# Main.net
KiCad netlist of a schematic drawn in Altium Designer
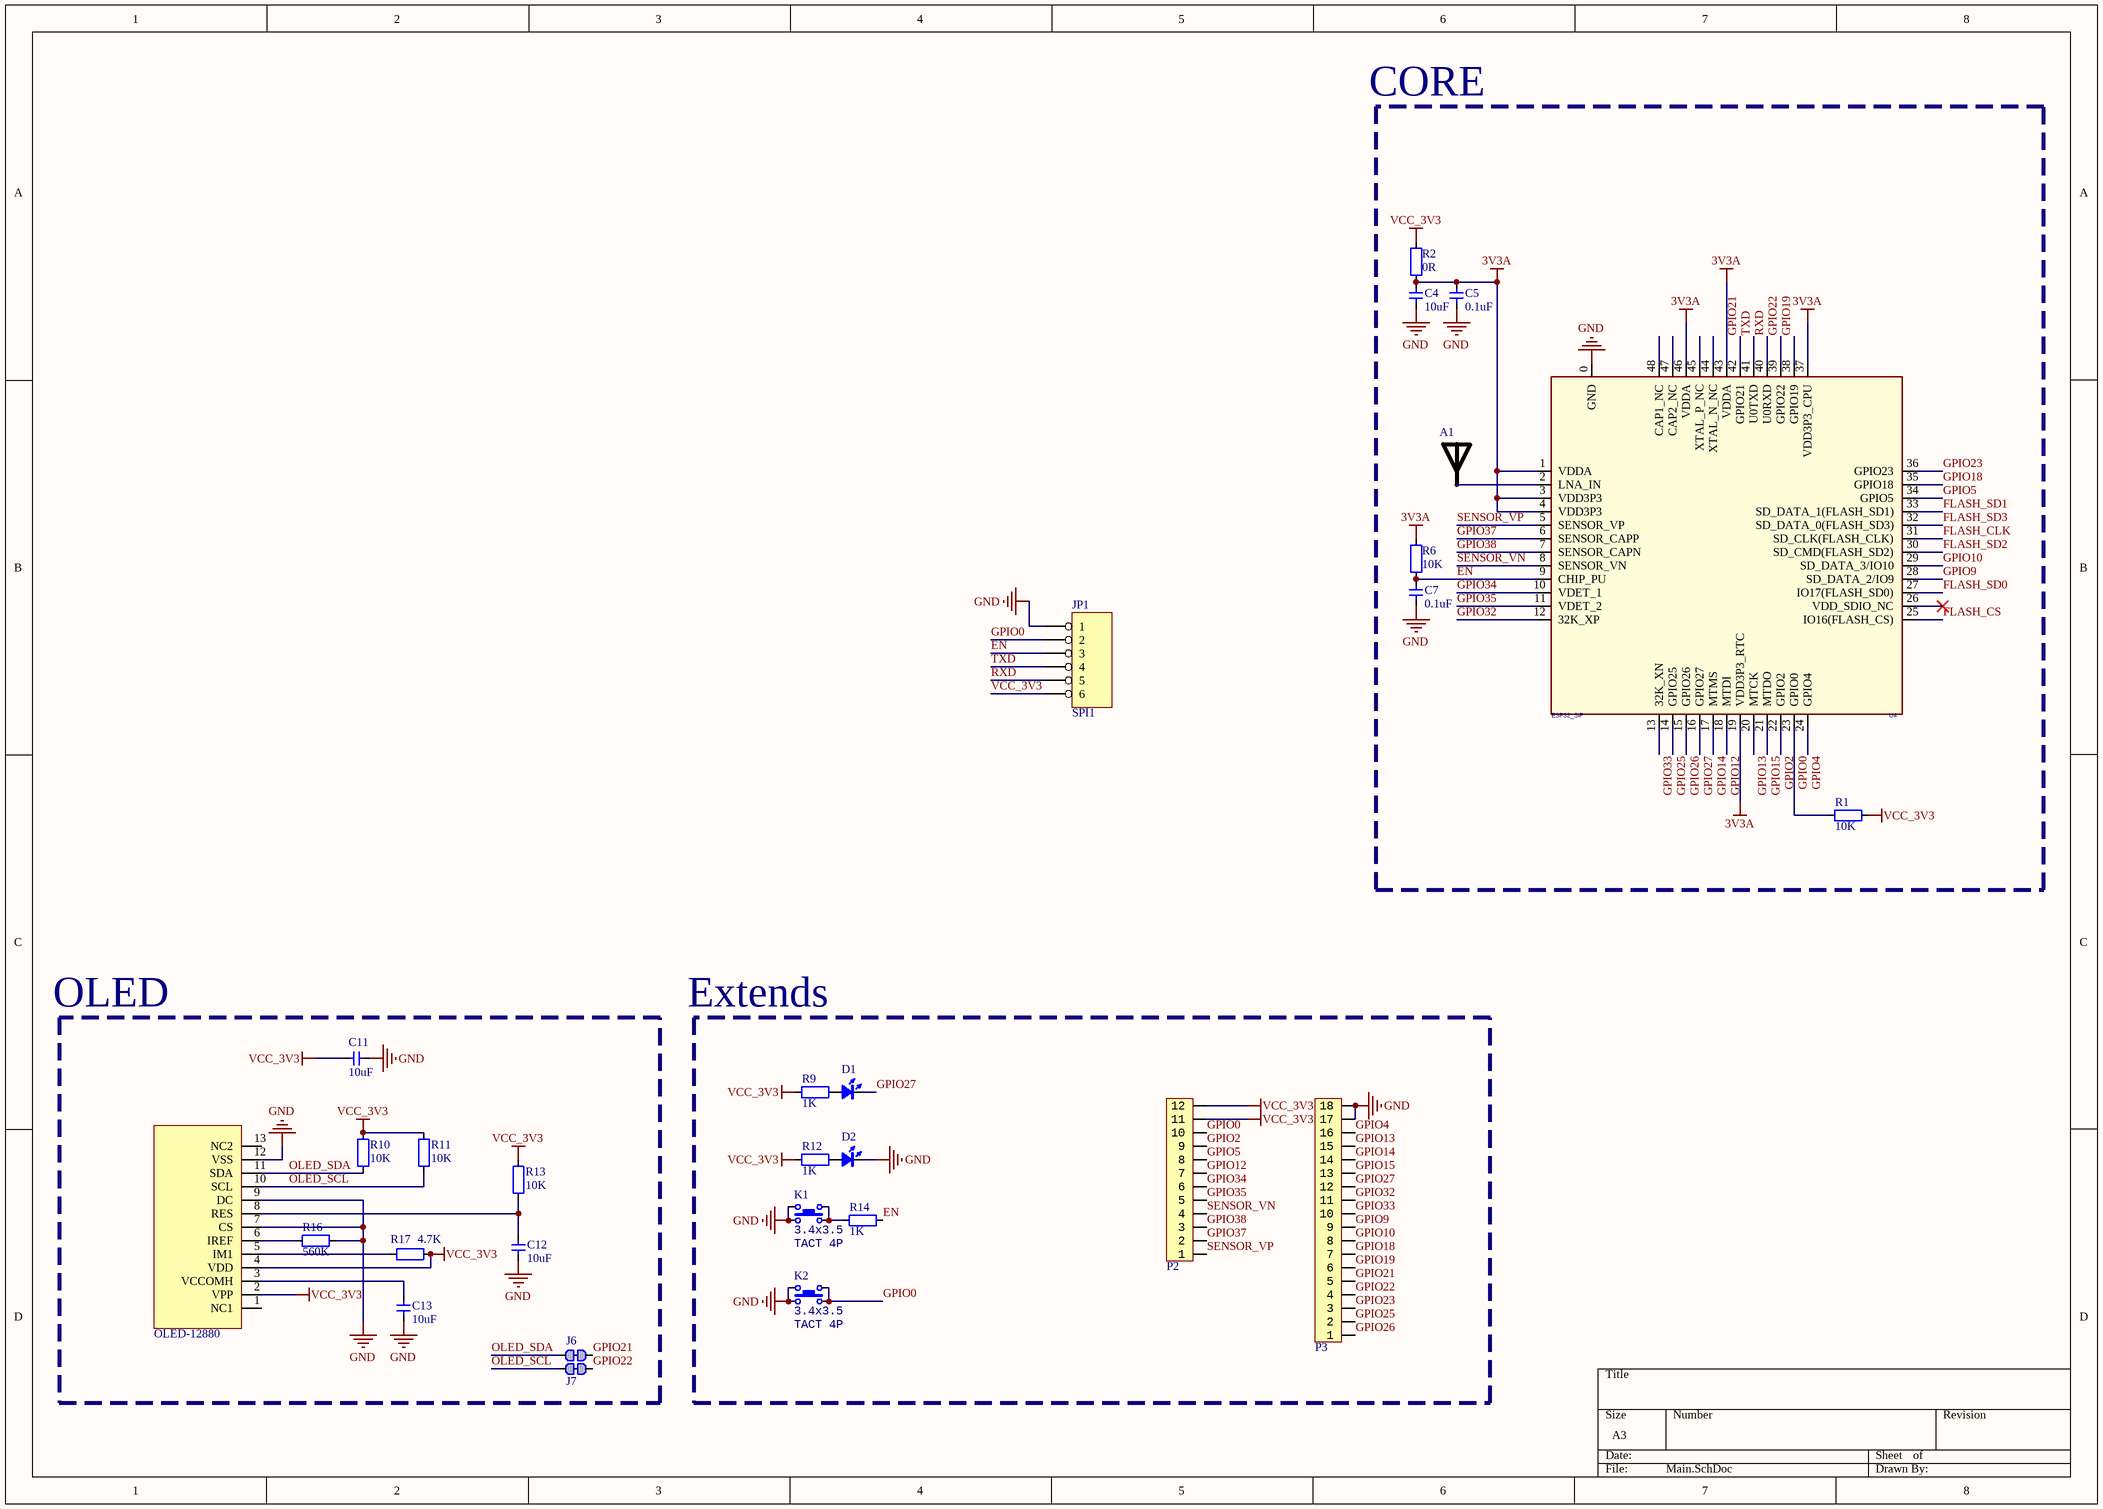
[diagram p0: Main.SchDoc]

(export (version "E")
  (design (tool "Eeschema 10.0.6"))
  (components
    (comp (ref "1")
      (value "OLED-12880")
      (footprint "OLED-12880")
      (libsource (lib "mLib") (part "OLED-12880"))
    )
    (comp (ref "A1")
      (value "RAINSUN")
      (footprint "ANT-Rainsun-AN5120")
      (libsource (lib "MyPcbLib") (part "ANT-Rainsun-AP5120"))
    )
    (comp (ref "C4")
      (value "10uF")
      (footprint "CAP_0402")
      (description "Capacitor")
      (libsource (lib "MyPcbLib") (part "电容-0402"))
    )
    (comp (ref "C5")
      (value "0.1uF")
      (footprint "CAP_0402")
      (description "Capacitor")
      (libsource (lib "MyPcbLib") (part "电容-0402"))
    )
    (comp (ref "C7")
      (value "0.1uF")
      (footprint "CAP_0402")
      (description "Capacitor")
      (libsource (lib "MyPcbLib") (part "电容-0402"))
    )
    (comp (ref "C11")
      (value "10uF")
      (footprint "CAP_0402")
      (description "Capacitor")
      (libsource (lib "MyPcbLib") (part "电容-0402"))
    )
    (comp (ref "C12")
      (value "10uF")
      (footprint "CAP_0402")
      (description "Capacitor")
      (libsource (lib "MyPcbLib") (part "电容-0402"))
    )
    (comp (ref "C13")
      (value "10uF")
      (footprint "CAP_0402")
      (description "Capacitor")
      (libsource (lib "MyPcbLib") (part "电容-0402"))
    )
    (comp (ref "D1")
      (value "color?")
      (footprint "LED_0402_RED")
      (description "LED")
      (libsource (lib "KitSprout") (part "LED_0402"))
    )
    (comp (ref "D2")
      (value "color?")
      (footprint "LED_0402_RED")
      (description "LED")
      (libsource (lib "KitSprout") (part "LED_0402"))
    )
    (comp (ref "J6")
      (value "跳线")
      (footprint "0402-0R")
      (description "Resistor")
      (fields (field (name "PUBLISHER") "Altium Limited"))
      (libsource (lib "MyPcbLib") (part "跳线"))
    )
    (comp (ref "J7")
      (value "跳线")
      (footprint "0402-0R")
      (description "Resistor")
      (fields (field (name "PUBLISHER") "Altium Limited"))
      (libsource (lib "MyPcbLib") (part "跳线"))
    )
    (comp (ref "JP1")
      (value "SPI1")
      (footprint "CONN-SMD_6P-P1.25_DEALON_1.25-6PWB")
      (libsource (lib "刘涛20200314") (part "HEADER 6"))
    )
    (comp (ref "K1")
      (value "3.4x3.5")
      (footprint "ButtonTACT_3.5*3.55_90")
      (description "Button")
      (fields (field (name "TYPE") "TACT 4P") (field (name "Comment") "TACT 4P"))
      (libsource (lib "KitSprout") (part "ButtonTACT"))
    )
    (comp (ref "K2")
      (value "3.4x3.5")
      (footprint "ButtonTACT_3.5*3.55_90")
      (description "Button")
      (fields (field (name "TYPE") "TACT 4P") (field (name "Comment") "TACT 4P"))
      (libsource (lib "KitSprout") (part "ButtonTACT"))
    )
    (comp (ref "P2")
      (value "HDR1x12_2.54")
      (footprint "HDR1X12_2.54_180")
      (description "Header")
      (libsource (lib "KitSprout") (part "HDR1x12_2.54"))
    )
    (comp (ref "P3")
      (value "HDR1x18_2.54")
      (footprint "HDR1X18_2.54_180")
      (description "Header")
      (libsource (lib "KitSprout") (part "HDR1x18_2.54"))
    )
    (comp (ref "R1")
      (value "10K")
      (footprint "RES_0402")
      (description "Resistor")
      (libsource (lib "") (part "电阻-0402_1"))
    )
    (comp (ref "R2")
      (value "0R")
      (footprint "RES_0402")
      (description "Resistor")
      (libsource (lib "") (part "电阻-0402_2"))
    )
    (comp (ref "R6")
      (value "10K")
      (footprint "RES_0402")
      (description "Resistor")
      (libsource (lib "") (part "电阻-0402_2"))
    )
    (comp (ref "R9")
      (value "1K")
      (footprint "RES_0402")
      (description "Resistor")
      (libsource (lib "") (part "电阻-0402_1"))
    )
    (comp (ref "R10")
      (value "10K")
      (footprint "RES_0402")
      (description "Resistor")
      (libsource (lib "MyPcbLib") (part "电阻-0402"))
    )
    (comp (ref "R11")
      (value "10K")
      (footprint "RES_0402")
      (description "Resistor")
      (libsource (lib "MyPcbLib") (part "电阻-0402"))
    )
    (comp (ref "R12")
      (value "1K")
      (footprint "RES_0402")
      (description "Resistor")
      (libsource (lib "") (part "电阻-0402_1"))
    )
    (comp (ref "R13")
      (value "10K")
      (footprint "RES_0402")
      (description "Resistor")
      (libsource (lib "MyPcbLib") (part "电阻-0402"))
    )
    (comp (ref "R14")
      (value "1K")
      (footprint "RES_0402")
      (description "Resistor")
      (libsource (lib "") (part "电阻-0402_1"))
    )
    (comp (ref "R16")
      (value "560K")
      (footprint "RES_0402")
      (description "Resistor")
      (libsource (lib "") (part "电阻-0402_1"))
    )
    (comp (ref "R17")
      (value "4.7K")
      (footprint "RES_0402")
      (description "Resistor")
      (libsource (lib "") (part "电阻-0402_1"))
    )
    (comp (ref "U4")
      (value "ESP32_SIP")
      (footprint "QFN-48_7X7")
      (libsource (lib "MyPcbLib") (part "ESP32-PICO"))
    )
  )
  (nets
    (net (code "1") (name "/EN") (class "Default")
      (node (ref "C7") (pin "1") (pinfunction "1_1") (pintype "passive"))
      (node (ref "JP1") (pin "3") (pinfunction "3_3") (pintype "passive"))
      (node (ref "R14") (pin "2") (pinfunction "2_2") (pintype "passive"))
      (node (ref "R6") (pin "2") (pinfunction "2_2") (pintype "passive"))
      (node (ref "U4") (pin "9") (pinfunction "CHIP_PU_9") (pintype "passive"))
    )
    (net (code "2") (name "/FLASH_CLK") (class "Default")
      (node (ref "U4") (pin "31") (pinfunction "SD_CLK(FLASH_CLK)_31") (pintype "passive"))
    )
    (net (code "3") (name "/FLASH_CS") (class "Default")
      (node (ref "U4") (pin "25") (pinfunction "IO16(FLASH_CS)_25") (pintype "passive"))
    )
    (net (code "4") (name "/FLASH_SD0") (class "Default")
      (node (ref "U4") (pin "27") (pinfunction "IO17(FLASH_SD0)_27") (pintype "passive"))
    )
    (net (code "5") (name "/FLASH_SD1") (class "Default")
      (node (ref "U4") (pin "33") (pinfunction "SD_DATA_1(FLASH_SD1)_33") (pintype "passive"))
    )
    (net (code "6") (name "/FLASH_SD2") (class "Default")
      (node (ref "U4") (pin "30") (pinfunction "SD_CMD(FLASH_SD2)_30") (pintype "passive"))
    )
    (net (code "7") (name "/FLASH_SD3") (class "Default")
      (node (ref "U4") (pin "32") (pinfunction "SD_DATA_0(FLASH_SD3)_32") (pintype "passive"))
    )
    (net (code "8") (name "/GPIO0") (class "Default")
      (node (ref "JP1") (pin "2") (pinfunction "2_2") (pintype "passive"))
      (node (ref "K2") (pin "2") (pinfunction "2_2") (pintype "passive"))
      (node (ref "K2") (pin "4") (pinfunction "4_4") (pintype "passive"))
      (node (ref "P2") (pin "10") (pinfunction "10_10") (pintype "passive"))
      (node (ref "R1") (pin "1") (pinfunction "1_1") (pintype "passive"))
      (node (ref "U4") (pin "23") (pinfunction "GPIO0_23") (pintype "passive"))
    )
    (net (code "9") (name "/GPIO2") (class "Default")
      (node (ref "P2") (pin "9") (pinfunction "9_9") (pintype "passive"))
      (node (ref "U4") (pin "22") (pinfunction "GPIO2_22") (pintype "passive"))
    )
    (net (code "10") (name "/GPIO4") (class "Default")
      (node (ref "P3") (pin "16") (pinfunction "16_16") (pintype "passive"))
      (node (ref "U4") (pin "24") (pinfunction "GPIO4_24") (pintype "passive"))
    )
    (net (code "11") (name "/GPIO5") (class "Default")
      (node (ref "P2") (pin "8") (pinfunction "8_8") (pintype "passive"))
      (node (ref "U4") (pin "34") (pinfunction "GPIO5_34") (pintype "passive"))
    )
    (net (code "12") (name "/GPIO9") (class "Default")
      (node (ref "P3") (pin "9") (pinfunction "9_9") (pintype "passive"))
      (node (ref "U4") (pin "28") (pinfunction "SD_DATA_2/IO9_28") (pintype "passive"))
    )
    (net (code "13") (name "/GPIO10") (class "Default")
      (node (ref "P3") (pin "8") (pinfunction "8_8") (pintype "passive"))
      (node (ref "U4") (pin "29") (pinfunction "SD_DATA_3/IO10_29") (pintype "passive"))
    )
    (net (code "14") (name "/GPIO12") (class "Default")
      (node (ref "P2") (pin "7") (pinfunction "7_7") (pintype "passive"))
      (node (ref "U4") (pin "18") (pinfunction "MTDI_18") (pintype "passive"))
    )
    (net (code "15") (name "/GPIO13") (class "Default")
      (node (ref "P3") (pin "15") (pinfunction "15_15") (pintype "passive"))
      (node (ref "U4") (pin "20") (pinfunction "MTCK_20") (pintype "passive"))
    )
    (net (code "16") (name "/GPIO14") (class "Default")
      (node (ref "P3") (pin "14") (pinfunction "14_14") (pintype "passive"))
      (node (ref "U4") (pin "17") (pinfunction "MTMS_17") (pintype "passive"))
    )
    (net (code "17") (name "/GPIO15") (class "Default")
      (node (ref "P3") (pin "13") (pinfunction "13_13") (pintype "passive"))
      (node (ref "U4") (pin "21") (pinfunction "MTDO_21") (pintype "passive"))
    )
    (net (code "18") (name "/GPIO18") (class "Default")
      (node (ref "P3") (pin "7") (pinfunction "7_7") (pintype "passive"))
      (node (ref "U4") (pin "35") (pinfunction "GPIO18_35") (pintype "passive"))
    )
    (net (code "19") (name "/GPIO19") (class "Default")
      (node (ref "P3") (pin "6") (pinfunction "6_6") (pintype "passive"))
      (node (ref "U4") (pin "38") (pinfunction "GPIO19_38") (pintype "passive"))
    )
    (net (code "20") (name "/GPIO21") (class "Default")
      (node (ref "J6") (pin "2") (pinfunction "2_2") (pintype "passive"))
      (node (ref "P3") (pin "5") (pinfunction "5_5") (pintype "passive"))
      (node (ref "U4") (pin "42") (pinfunction "GPIO21_42") (pintype "passive"))
    )
    (net (code "21") (name "/GPIO22") (class "Default")
      (node (ref "J7") (pin "2") (pinfunction "2_2") (pintype "passive"))
      (node (ref "P3") (pin "4") (pinfunction "4_4") (pintype "passive"))
      (node (ref "U4") (pin "39") (pinfunction "GPIO22_39") (pintype "passive"))
    )
    (net (code "22") (name "/GPIO23") (class "Default")
      (node (ref "P3") (pin "3") (pinfunction "3_3") (pintype "passive"))
      (node (ref "U4") (pin "36") (pinfunction "GPIO23_36") (pintype "passive"))
    )
    (net (code "23") (name "/GPIO25") (class "Default")
      (node (ref "P3") (pin "2") (pinfunction "2_2") (pintype "passive"))
      (node (ref "U4") (pin "14") (pinfunction "GPIO25_14") (pintype "passive"))
    )
    (net (code "24") (name "/GPIO26") (class "Default")
      (node (ref "P3") (pin "1") (pinfunction "1_1") (pintype "passive"))
      (node (ref "U4") (pin "15") (pinfunction "GPIO26_15") (pintype "passive"))
    )
    (net (code "25") (name "/GPIO27") (class "Default")
      (node (ref "D1") (pin "2") (pinfunction "K_2") (pintype "passive"))
      (node (ref "P3") (pin "12") (pinfunction "12_12") (pintype "passive"))
      (node (ref "U4") (pin "16") (pinfunction "GPIO27_16") (pintype "passive"))
    )
    (net (code "26") (name "/GPIO32") (class "Default")
      (node (ref "P3") (pin "11") (pinfunction "11_11") (pintype "passive"))
      (node (ref "U4") (pin "12") (pinfunction "32K_XP_12") (pintype "passive"))
    )
    (net (code "27") (name "/GPIO33") (class "Default")
      (node (ref "P3") (pin "10") (pinfunction "10_10") (pintype "passive"))
      (node (ref "U4") (pin "13") (pinfunction "32K_XN_13") (pintype "passive"))
    )
    (net (code "28") (name "/GPIO34") (class "Default")
      (node (ref "P2") (pin "6") (pinfunction "6_6") (pintype "passive"))
      (node (ref "U4") (pin "10") (pinfunction "VDET_1_10") (pintype "passive"))
    )
    (net (code "29") (name "/GPIO35") (class "Default")
      (node (ref "P2") (pin "5") (pinfunction "5_5") (pintype "passive"))
      (node (ref "U4") (pin "11") (pinfunction "VDET_2_11") (pintype "passive"))
    )
    (net (code "30") (name "/GPIO37") (class "Default")
      (node (ref "P2") (pin "2") (pinfunction "2_2") (pintype "passive"))
      (node (ref "U4") (pin "6") (pinfunction "SENSOR_CAPP_6") (pintype "passive"))
    )
    (net (code "31") (name "/GPIO38") (class "Default")
      (node (ref "P2") (pin "3") (pinfunction "3_3") (pintype "passive"))
      (node (ref "U4") (pin "7") (pinfunction "SENSOR_CAPN_7") (pintype "passive"))
    )
    (net (code "32") (name "/OLED_SCL") (class "Default")
      (node (ref "1") (pin "10") (pinfunction "SCL_10") (pintype "passive"))
      (node (ref "J7") (pin "1") (pinfunction "1_1") (pintype "passive"))
      (node (ref "R11") (pin "1") (pinfunction "1_1") (pintype "passive"))
    )
    (net (code "33") (name "/OLED_SDA") (class "Default")
      (node (ref "1") (pin "11") (pinfunction "SDA_11") (pintype "passive"))
      (node (ref "J6") (pin "1") (pinfunction "1_1") (pintype "passive"))
      (node (ref "R10") (pin "1") (pinfunction "1_1") (pintype "passive"))
    )
    (net (code "34") (name "/RXD") (class "Default")
      (node (ref "JP1") (pin "5") (pinfunction "5_5") (pintype "passive"))
      (node (ref "U4") (pin "40") (pinfunction "U0RXD_40") (pintype "power_in"))
    )
    (net (code "35") (name "/SENSOR_VN") (class "Default")
      (node (ref "P2") (pin "4") (pinfunction "4_4") (pintype "passive"))
      (node (ref "U4") (pin "8") (pinfunction "SENSOR_VN_8") (pintype "passive"))
    )
    (net (code "36") (name "/SENSOR_VP") (class "Default")
      (node (ref "P2") (pin "1") (pinfunction "1_1") (pintype "passive"))
      (node (ref "U4") (pin "5") (pinfunction "SENSOR_VP_5") (pintype "passive"))
    )
    (net (code "37") (name "/TXD") (class "Default")
      (node (ref "JP1") (pin "4") (pinfunction "4_4") (pintype "passive"))
      (node (ref "U4") (pin "41") (pinfunction "U0TXD_41") (pintype "power_in"))
    )
    (net (code "38") (name "3V3A") (class "Default")
      (node (ref "C4") (pin "2") (pinfunction "2_2") (pintype "passive"))
      (node (ref "C5") (pin "2") (pinfunction "2_2") (pintype "passive"))
      (node (ref "R2") (pin "2") (pinfunction "2_2") (pintype "passive"))
      (node (ref "R6") (pin "1") (pinfunction "1_1") (pintype "passive"))
      (node (ref "U4") (pin "1") (pinfunction "VDDA_1") (pintype "power_in"))
      (node (ref "U4") (pin "19") (pinfunction "VDD3P3_RTC_19") (pintype "power_in"))
      (node (ref "U4") (pin "3") (pinfunction "VDD3P3_3") (pintype "power_in"))
      (node (ref "U4") (pin "37") (pinfunction "VDD3P3_CPU_37") (pintype "power_in"))
      (node (ref "U4") (pin "4") (pinfunction "VDD3P3_4") (pintype "power_in"))
      (node (ref "U4") (pin "43") (pinfunction "VDDA_43") (pintype "power_in"))
      (node (ref "U4") (pin "46") (pinfunction "VDDA_46") (pintype "power_in"))
    )
    (net (code "39") (name "GND") (class "Default")
      (node (ref "1") (pin "12") (pinfunction "VSS_12") (pintype "passive"))
      (node (ref "1") (pin "7") (pinfunction "CS_7") (pintype "passive"))
      (node (ref "1") (pin "9") (pinfunction "DC_9") (pintype "passive"))
      (node (ref "C11") (pin "1") (pinfunction "1_1") (pintype "passive"))
      (node (ref "C12") (pin "1") (pinfunction "1_1") (pintype "passive"))
      (node (ref "C13") (pin "1") (pinfunction "1_1") (pintype "passive"))
      (node (ref "C4") (pin "1") (pinfunction "1_1") (pintype "passive"))
      (node (ref "C5") (pin "1") (pinfunction "1_1") (pintype "passive"))
      (node (ref "C7") (pin "2") (pinfunction "2_2") (pintype "passive"))
      (node (ref "D2") (pin "2") (pinfunction "K_2") (pintype "passive"))
      (node (ref "JP1") (pin "1") (pinfunction "1_1") (pintype "passive"))
      (node (ref "K1") (pin "1") (pinfunction "1_1") (pintype "passive"))
      (node (ref "K1") (pin "3") (pinfunction "3_3") (pintype "passive"))
      (node (ref "K2") (pin "1") (pinfunction "1_1") (pintype "passive"))
      (node (ref "K2") (pin "3") (pinfunction "3_3") (pintype "passive"))
      (node (ref "P3") (pin "17") (pinfunction "17_17") (pintype "passive"))
      (node (ref "P3") (pin "18") (pinfunction "18_18") (pintype "passive"))
      (node (ref "R16") (pin "2") (pinfunction "2_2") (pintype "passive"))
      (node (ref "U4") (pin "0") (pinfunction "GND_0") (pintype "power_in"))
    )
    (net (code "40") (name "Net-(1-IM1)") (class "Default")
      (node (ref "1") (pin "5") (pinfunction "IM1_5") (pintype "passive"))
      (node (ref "R17") (pin "1") (pinfunction "1_1") (pintype "passive"))
    )
    (net (code "41") (name "Net-(1-IREF)") (class "Default")
      (node (ref "1") (pin "6") (pinfunction "IREF_6") (pintype "passive"))
      (node (ref "R16") (pin "1") (pinfunction "1_1") (pintype "passive"))
    )
    (net (code "42") (name "Net-(1-RES)") (class "Default")
      (node (ref "1") (pin "8") (pinfunction "RES_8") (pintype "passive"))
      (node (ref "C12") (pin "2") (pinfunction "2_2") (pintype "passive"))
      (node (ref "R13") (pin "1") (pinfunction "1_1") (pintype "passive"))
    )
    (net (code "43") (name "Net-(1-VCCOMH)") (class "Default")
      (node (ref "1") (pin "3") (pinfunction "VCCOMH_3") (pintype "passive"))
      (node (ref "C13") (pin "2") (pinfunction "2_2") (pintype "passive"))
    )
    (net (code "44") (name "Net-(D1-A)") (class "Default")
      (node (ref "D1") (pin "1") (pinfunction "A_1") (pintype "passive"))
      (node (ref "R9") (pin "2") (pinfunction "2_2") (pintype "passive"))
    )
    (net (code "45") (name "Net-(D2-A)") (class "Default")
      (node (ref "D2") (pin "1") (pinfunction "A_1") (pintype "passive"))
      (node (ref "R12") (pin "2") (pinfunction "2_2") (pintype "passive"))
    )
    (net (code "46") (name "Net-(K1-Pad2)") (class "Default")
      (node (ref "K1") (pin "2") (pinfunction "2_2") (pintype "passive"))
      (node (ref "K1") (pin "4") (pinfunction "4_4") (pintype "passive"))
      (node (ref "R14") (pin "1") (pinfunction "1_1") (pintype "passive"))
    )
    (net (code "47") (name "Net-(U4-LNA_IN)") (class "Default")
      (node (ref "A1") (pin "1") (pinfunction "1_1") (pintype "passive"))
      (node (ref "U4") (pin "2") (pinfunction "LNA_IN_2") (pintype "passive"))
    )
    (net (code "48") (name "VCC_3V3") (class "Default")
      (node (ref "1") (pin "2") (pinfunction "VPP_2") (pintype "passive"))
      (node (ref "1") (pin "4") (pinfunction "VDD_4") (pintype "passive"))
      (node (ref "C11") (pin "2") (pinfunction "2_2") (pintype "passive"))
      (node (ref "JP1") (pin "6") (pinfunction "6_6") (pintype "passive"))
      (node (ref "P2") (pin "11") (pinfunction "11_11") (pintype "passive"))
      (node (ref "P2") (pin "12") (pinfunction "12_12") (pintype "passive"))
      (node (ref "R1") (pin "2") (pinfunction "2_2") (pintype "passive"))
      (node (ref "R10") (pin "2") (pinfunction "2_2") (pintype "passive"))
      (node (ref "R11") (pin "2") (pinfunction "2_2") (pintype "passive"))
      (node (ref "R12") (pin "1") (pinfunction "1_1") (pintype "passive"))
      (node (ref "R13") (pin "2") (pinfunction "2_2") (pintype "passive"))
      (node (ref "R17") (pin "2") (pinfunction "2_2") (pintype "passive"))
      (node (ref "R2") (pin "1") (pinfunction "1_1") (pintype "passive"))
      (node (ref "R9") (pin "1") (pinfunction "1_1") (pintype "passive"))
    )
    (net (code "49") (name "unconnected-(1-NC1-Pad1)") (class "Default")
      (node (ref "1") (pin "1") (pinfunction "NC1_1") (pintype "passive"))
    )
    (net (code "50") (name "unconnected-(1-NC2-Pad13)") (class "Default")
      (node (ref "1") (pin "13") (pinfunction "NC2_13") (pintype "passive"))
    )
    (net (code "51") (name "unconnected-(U4-CAP1_NC-Pad48)") (class "Default")
      (node (ref "U4") (pin "48") (pinfunction "CAP1_NC_48") (pintype "passive"))
    )
    (net (code "52") (name "unconnected-(U4-CAP2_NC-Pad47)") (class "Default")
      (node (ref "U4") (pin "47") (pinfunction "CAP2_NC_47") (pintype "passive"))
    )
    (net (code "53") (name "unconnected-(U4-VDD_SDIO_NC-Pad26)") (class "Default")
      (node (ref "U4") (pin "26") (pinfunction "VDD_SDIO_NC_26") (pintype "passive+no_connect"))
    )
    (net (code "54") (name "unconnected-(U4-XTAL_N_NC-Pad44)") (class "Default")
      (node (ref "U4") (pin "44") (pinfunction "XTAL_N_NC_44") (pintype "passive"))
    )
    (net (code "55") (name "unconnected-(U4-XTAL_P_NC-Pad45)") (class "Default")
      (node (ref "U4") (pin "45") (pinfunction "XTAL_P_NC_45") (pintype "passive"))
    )
  )
)
